# schematic.net
KiCad netlist of a schematic drawn in Altium Designer
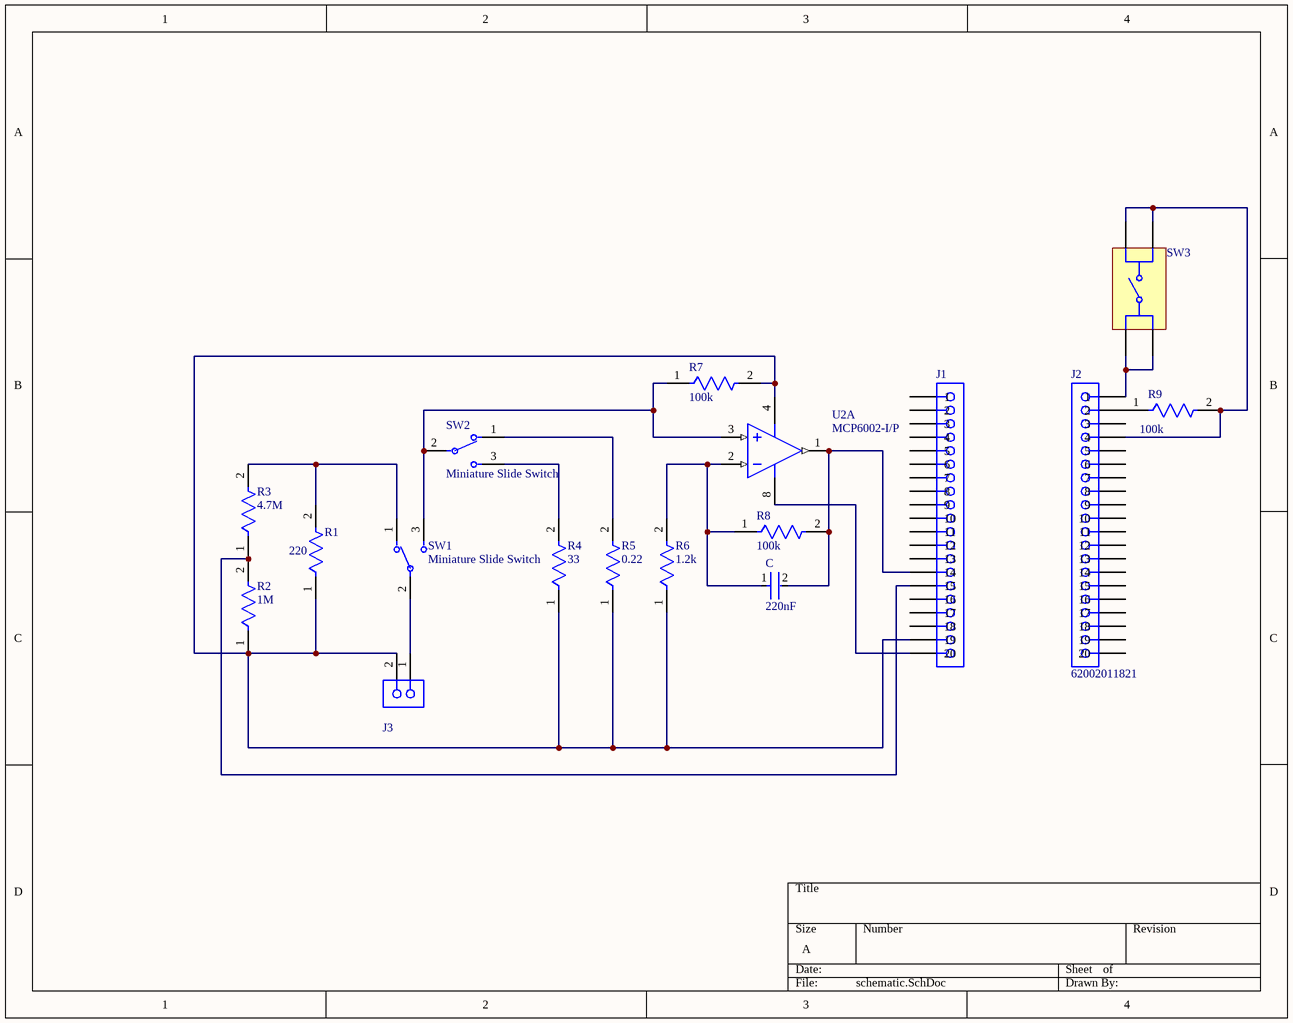
[diagram p0: schematic.SchDoc]

(export (version "E")
  (design (tool "Eeschema 10.0.6"))
  (components
    (comp (ref "C")
      (value "220nF")
      (footprint "FP-GRM155-0_05-MFG")
      (description "Multilayer Ceramic Capacitor 0.22uF 10% 63V X5R 0402 Paper T/R")
      (libsource (lib "Altium Content Vault") (part "b4654b650e69147ec39a6b967a45e02"))
    )
    (comp (ref "J1")
      (value "Vertical Socket Header")
      (footprint "62002011821")
      (libsource (lib "Altium Content Vault") (part "Header_Female_1R_20P"))
    )
    (comp (ref "J2")
      (value "62002011821")
      (footprint "62002011821")
      (libsource (lib "Altium Content Vault") (part "Header_Female_1R_20P"))
    )
    (comp (ref "J3")
      (value "Screw Terminal Block")
      (footprint "691417320002S")
      (libsource (lib "Altium Content Vault") (part "TBL - 1R - 02P - Female"))
    )
    (comp (ref "R1")
      (value "220")
      (footprint "FP-PTF56-MFG")
      (description "Res Metal Film 220 Ohm 1% ± 5ppm/°C 1/8W Axial Leaded T/R")
      (fields (field (name "TOLERANCE") "1%"))
      (libsource (lib "Altium Content Vault") (part "1029c3af85768c4190bb7ad29bc67b5"))
    )
    (comp (ref "R2")
      (value "1M")
      (footprint "FP-PTF56-MFG")
      (description "Res Metal Film 1MOhm 1% ± 5ppm/°C 1/8W Axial Leaded T/R")
      (fields (field (name "TOLERANCE") "1%"))
      (libsource (lib "Altium Content Vault") (part "1029c3af85768c4190bb7ad29bc67b5"))
    )
    (comp (ref "R3")
      (value "4.7M")
      (footprint "FP-PTF56-MFG")
      (description "Res Metal Film 4.7MOhm 1% ± 5ppm/°C 1/8W Axial Leaded T/R")
      (fields (field (name "TOLERANCE") "1%"))
      (libsource (lib "Altium Content Vault") (part "1029c3af85768c4190bb7ad29bc67b5"))
    )
    (comp (ref "R4")
      (value "33")
      (footprint "FP-PTF56-MFG")
      (description "Res Metal Film 33Ohm 1% ± 5ppm/°C 1/8W Axial Leaded T/R")
      (fields (field (name "TOLERANCE") "1%"))
      (libsource (lib "Altium Content Vault") (part "1029c3af85768c4190bb7ad29bc67b5"))
    )
    (comp (ref "R5")
      (value "0.22")
      (footprint "FP-PTF56-MFG")
      (description "Res Metal Film 0.22Ohm 1% ± 5ppm/°C 1/8W Axial Leaded T/R")
      (fields (field (name "TOLERANCE") "1%"))
      (libsource (lib "Altium Content Vault") (part "1029c3af85768c4190bb7ad29bc67b5"))
    )
    (comp (ref "R6")
      (value "1.2k")
      (footprint "FP-PTF56-MFG")
      (description "Res Metal Film 1.2kOhm 1% ± 5ppm/°C 1/8W Axial Leaded T/R")
      (fields (field (name "TOLERANCE") "1%"))
      (libsource (lib "Altium Content Vault") (part "1029c3af85768c4190bb7ad29bc67b5"))
    )
    (comp (ref "R7")
      (value "100k")
      (footprint "FP-PTF56-MFG")
      (description "Res Metal Film 100kOhm 1% ± 5ppm/°C 1/8W Axial Leaded T/R")
      (fields (field (name "TOLERANCE") "1%"))
      (libsource (lib "Altium Content Vault") (part "1029c3af85768c4190bb7ad29bc67b5"))
    )
    (comp (ref "R8")
      (value "100k")
      (footprint "FP-PTF56-MFG")
      (description "Res Metal Film 100kOhm 1% ± 5ppm/°C 1/8W Axial Leaded T/R")
      (fields (field (name "TOLERANCE") "1%"))
      (libsource (lib "Altium Content Vault") (part "1029c3af85768c4190bb7ad29bc67b5"))
    )
    (comp (ref "R9")
      (value "100k")
      (footprint "FP-PTF56-MFG")
      (description "PTF56250K00FZEB Res Metal Film 250kOhm 1% ± 5ppm/°C 1/8W Axial Leaded T/R")
      (fields (field (name "TOLERANCE") "1%"))
      (libsource (lib "Altium Content Vault") (part "1029c3af85768c4190bb7ad29bc67b5"))
    )
    (comp (ref "SW1")
      (value "Miniature Slide Switch")
      (footprint "FP-1101M2S3CGE2-MFG")
      (description "SWITCH SLIDE SPDT 6A 120V")
      (fields
        (field (name "MANUFACTURER") "C&K Components")
        (field (name "OCTOPART") "https://octopart.com/1101m2s3cge2-c%26k+components-2817222")
      )
      (libsource (lib "Altium Content Vault") (part "7fcaa069a19c2acd609832313418d7c"))
    )
    (comp (ref "SW2")
      (value "Miniature Slide Switch")
      (footprint "FP-1101M2S3CGE2-MFG")
      (description "SWITCH SLIDE SPDT 6A 120V")
      (fields
        (field (name "MANUFACTURER") "C&K Components")
        (field (name "OCTOPART") "https://octopart.com/1101m2s3cge2-c%26k+components-2817222")
      )
      (libsource (lib "Altium Content Vault") (part "7fcaa069a19c2acd609832313418d7c"))
    )
    (comp (ref "SW3")
      (value "Push Button")
      (footprint "430473035826")
      (description "Switch Tactile Spst-no 0.05A 12V")
      (libsource (lib "Altium Content Vault") (part "SPST-NO_4P"))
    )
    (comp (ref "U2")
      (value "MCP6002-I/P")
      (footprint "PDIP300-P8")
      (description "None")
      (libsource (lib "Altium Content Vault") (part "AMP-OPA-MCP6002-IL8"))
    )
  )
  (nets
    (net (code "1") (name "Net-(J1-Pad15)") (class "Default")
      (node (ref "J1") (pin "15") (pinfunction "15_15") (pintype "passive"))
      (node (ref "R2") (pin "2") (pinfunction "2_2") (pintype "passive"))
      (node (ref "R3") (pin "1") (pinfunction "1_1") (pintype "passive"))
    )
    (net (code "2") (name "Net-(J2-Pad1)") (class "Default")
      (node (ref "J2") (pin "1") (pinfunction "1_1") (pintype "passive"))
      (node (ref "SW3") (pin "A1") (pinfunction "A1_A1") (pintype "passive"))
      (node (ref "SW3") (pin "A2") (pinfunction "A2_A2") (pintype "passive"))
    )
    (net (code "3") (name "Net-(J2-Pad2)") (class "Default")
      (node (ref "J2") (pin "2") (pinfunction "2_2") (pintype "passive"))
      (node (ref "R9") (pin "1") (pinfunction "1_1") (pintype "passive"))
    )
    (net (code "4") (name "Net-(J2-Pad4)") (class "Default")
      (node (ref "J2") (pin "4") (pinfunction "4_4") (pintype "passive"))
      (node (ref "R9") (pin "2") (pinfunction "2_2") (pintype "passive"))
      (node (ref "SW3") (pin "B1") (pinfunction "B1_B1") (pintype "passive"))
      (node (ref "SW3") (pin "B2") (pinfunction "B2_B2") (pintype "passive"))
    )
    (net (code "5") (name "Net-(R1-Pad2)") (class "Default")
      (node (ref "R1") (pin "2") (pinfunction "2_2") (pintype "passive"))
      (node (ref "R3") (pin "2") (pinfunction "2_2") (pintype "passive"))
      (node (ref "SW1") (pin "1") (pinfunction "1_1") (pintype "passive"))
    )
    (net (code "6") (name "Net-(R4-Pad2)") (class "Default")
      (node (ref "R4") (pin "2") (pinfunction "2_2") (pintype "passive"))
      (node (ref "SW2") (pin "3") (pinfunction "3_3") (pintype "passive"))
    )
    (net (code "7") (name "Net-(R5-Pad2)") (class "Default")
      (node (ref "R5") (pin "2") (pinfunction "2_2") (pintype "passive"))
      (node (ref "SW2") (pin "1") (pinfunction "1_1") (pintype "passive"))
    )
    (net (code "8") (name "Net-(SW1-COMM)") (class "Default")
      (node (ref "J3") (pin "1") (pinfunction "1_1") (pintype "passive"))
      (node (ref "SW1") (pin "2") (pinfunction "COMM_2") (pintype "passive"))
    )
    (net (code "9") (name "Net-(SW2-COMM)") (class "Default")
      (node (ref "R7") (pin "1") (pinfunction "1_1") (pintype "passive"))
      (node (ref "SW1") (pin "3") (pinfunction "3_3") (pintype "passive"))
      (node (ref "SW2") (pin "2") (pinfunction "COMM_2") (pintype "passive"))
      (node (ref "U2") (pin "3") (pinfunction "VINA+_3") (pintype "input"))
    )
    (net (code "10") (name "Net-(U2A-VDD)") (class "Default")
      (node (ref "J1") (pin "20") (pinfunction "20_20") (pintype "passive"))
      (node (ref "U2") (pin "8") (pinfunction "VDD_8") (pintype "power_in"))
    )
    (net (code "11") (name "Net-(U2A-VINA-)") (class "Default")
      (node (ref "C") (pin "1") (pinfunction "1_1") (pintype "passive"))
      (node (ref "R6") (pin "2") (pinfunction "2_2") (pintype "passive"))
      (node (ref "R8") (pin "1") (pinfunction "1_1") (pintype "passive"))
      (node (ref "U2") (pin "2") (pinfunction "VINA-_2") (pintype "input"))
    )
    (net (code "12") (name "Net-(U2A-VOUTA)") (class "Default")
      (node (ref "C") (pin "2") (pinfunction "2_2") (pintype "passive"))
      (node (ref "J1") (pin "14") (pinfunction "14_14") (pintype "passive"))
      (node (ref "R8") (pin "2") (pinfunction "2_2") (pintype "passive"))
      (node (ref "U2") (pin "1") (pinfunction "VOUTA_1") (pintype "output"))
    )
    (net (code "13") (name "Net-(U2A-VSS)") (class "Default")
      (node (ref "J1") (pin "19") (pinfunction "19_19") (pintype "passive"))
      (node (ref "J3") (pin "2") (pinfunction "2_2") (pintype "passive"))
      (node (ref "R1") (pin "1") (pinfunction "1_1") (pintype "passive"))
      (node (ref "R2") (pin "1") (pinfunction "1_1") (pintype "passive"))
      (node (ref "R4") (pin "1") (pinfunction "1_1") (pintype "passive"))
      (node (ref "R5") (pin "1") (pinfunction "1_1") (pintype "passive"))
      (node (ref "R6") (pin "1") (pinfunction "1_1") (pintype "passive"))
      (node (ref "R7") (pin "2") (pinfunction "2_2") (pintype "passive"))
      (node (ref "U2") (pin "4") (pinfunction "VSS_4") (pintype "power_in"))
    )
    (net (code "14") (name "unconnected-(J1-Pad1)") (class "Default")
      (node (ref "J1") (pin "1") (pinfunction "1_1") (pintype "passive"))
    )
    (net (code "15") (name "unconnected-(J1-Pad2)") (class "Default")
      (node (ref "J1") (pin "2") (pinfunction "2_2") (pintype "passive"))
    )
    (net (code "16") (name "unconnected-(J1-Pad3)") (class "Default")
      (node (ref "J1") (pin "3") (pinfunction "3_3") (pintype "passive"))
    )
    (net (code "17") (name "unconnected-(J1-Pad4)") (class "Default")
      (node (ref "J1") (pin "4") (pinfunction "4_4") (pintype "passive"))
    )
    (net (code "18") (name "unconnected-(J1-Pad5)") (class "Default")
      (node (ref "J1") (pin "5") (pinfunction "5_5") (pintype "passive"))
    )
    (net (code "19") (name "unconnected-(J1-Pad6)") (class "Default")
      (node (ref "J1") (pin "6") (pinfunction "6_6") (pintype "passive"))
    )
    (net (code "20") (name "unconnected-(J1-Pad7)") (class "Default")
      (node (ref "J1") (pin "7") (pinfunction "7_7") (pintype "passive"))
    )
    (net (code "21") (name "unconnected-(J1-Pad8)") (class "Default")
      (node (ref "J1") (pin "8") (pinfunction "8_8") (pintype "passive"))
    )
    (net (code "22") (name "unconnected-(J1-Pad9)") (class "Default")
      (node (ref "J1") (pin "9") (pinfunction "9_9") (pintype "passive"))
    )
    (net (code "23") (name "unconnected-(J1-Pad10)") (class "Default")
      (node (ref "J1") (pin "10") (pinfunction "10_10") (pintype "passive"))
    )
    (net (code "24") (name "unconnected-(J1-Pad11)") (class "Default")
      (node (ref "J1") (pin "11") (pinfunction "11_11") (pintype "passive"))
    )
    (net (code "25") (name "unconnected-(J1-Pad12)") (class "Default")
      (node (ref "J1") (pin "12") (pinfunction "12_12") (pintype "passive"))
    )
    (net (code "26") (name "unconnected-(J1-Pad13)") (class "Default")
      (node (ref "J1") (pin "13") (pinfunction "13_13") (pintype "passive"))
    )
    (net (code "27") (name "unconnected-(J1-Pad16)") (class "Default")
      (node (ref "J1") (pin "16") (pinfunction "16_16") (pintype "passive"))
    )
    (net (code "28") (name "unconnected-(J1-Pad17)") (class "Default")
      (node (ref "J1") (pin "17") (pinfunction "17_17") (pintype "passive"))
    )
    (net (code "29") (name "unconnected-(J1-Pad18)") (class "Default")
      (node (ref "J1") (pin "18") (pinfunction "18_18") (pintype "passive"))
    )
    (net (code "30") (name "unconnected-(J2-Pad3)") (class "Default")
      (node (ref "J2") (pin "3") (pinfunction "3_3") (pintype "passive"))
    )
    (net (code "31") (name "unconnected-(J2-Pad5)") (class "Default")
      (node (ref "J2") (pin "5") (pinfunction "5_5") (pintype "passive"))
    )
    (net (code "32") (name "unconnected-(J2-Pad6)") (class "Default")
      (node (ref "J2") (pin "6") (pinfunction "6_6") (pintype "passive"))
    )
    (net (code "33") (name "unconnected-(J2-Pad7)") (class "Default")
      (node (ref "J2") (pin "7") (pinfunction "7_7") (pintype "passive"))
    )
    (net (code "34") (name "unconnected-(J2-Pad8)") (class "Default")
      (node (ref "J2") (pin "8") (pinfunction "8_8") (pintype "passive"))
    )
    (net (code "35") (name "unconnected-(J2-Pad9)") (class "Default")
      (node (ref "J2") (pin "9") (pinfunction "9_9") (pintype "passive"))
    )
    (net (code "36") (name "unconnected-(J2-Pad10)") (class "Default")
      (node (ref "J2") (pin "10") (pinfunction "10_10") (pintype "passive"))
    )
    (net (code "37") (name "unconnected-(J2-Pad11)") (class "Default")
      (node (ref "J2") (pin "11") (pinfunction "11_11") (pintype "passive"))
    )
    (net (code "38") (name "unconnected-(J2-Pad12)") (class "Default")
      (node (ref "J2") (pin "12") (pinfunction "12_12") (pintype "passive"))
    )
    (net (code "39") (name "unconnected-(J2-Pad13)") (class "Default")
      (node (ref "J2") (pin "13") (pinfunction "13_13") (pintype "passive"))
    )
    (net (code "40") (name "unconnected-(J2-Pad14)") (class "Default")
      (node (ref "J2") (pin "14") (pinfunction "14_14") (pintype "passive"))
    )
    (net (code "41") (name "unconnected-(J2-Pad15)") (class "Default")
      (node (ref "J2") (pin "15") (pinfunction "15_15") (pintype "passive"))
    )
    (net (code "42") (name "unconnected-(J2-Pad16)") (class "Default")
      (node (ref "J2") (pin "16") (pinfunction "16_16") (pintype "passive"))
    )
    (net (code "43") (name "unconnected-(J2-Pad17)") (class "Default")
      (node (ref "J2") (pin "17") (pinfunction "17_17") (pintype "passive"))
    )
    (net (code "44") (name "unconnected-(J2-Pad18)") (class "Default")
      (node (ref "J2") (pin "18") (pinfunction "18_18") (pintype "passive"))
    )
    (net (code "45") (name "unconnected-(J2-Pad19)") (class "Default")
      (node (ref "J2") (pin "19") (pinfunction "19_19") (pintype "passive"))
    )
    (net (code "46") (name "unconnected-(J2-Pad20)") (class "Default")
      (node (ref "J2") (pin "20") (pinfunction "20_20") (pintype "passive"))
    )
  )
)
